# ch634x.net
KiCad netlist of a schematic drawn in Altium Designer
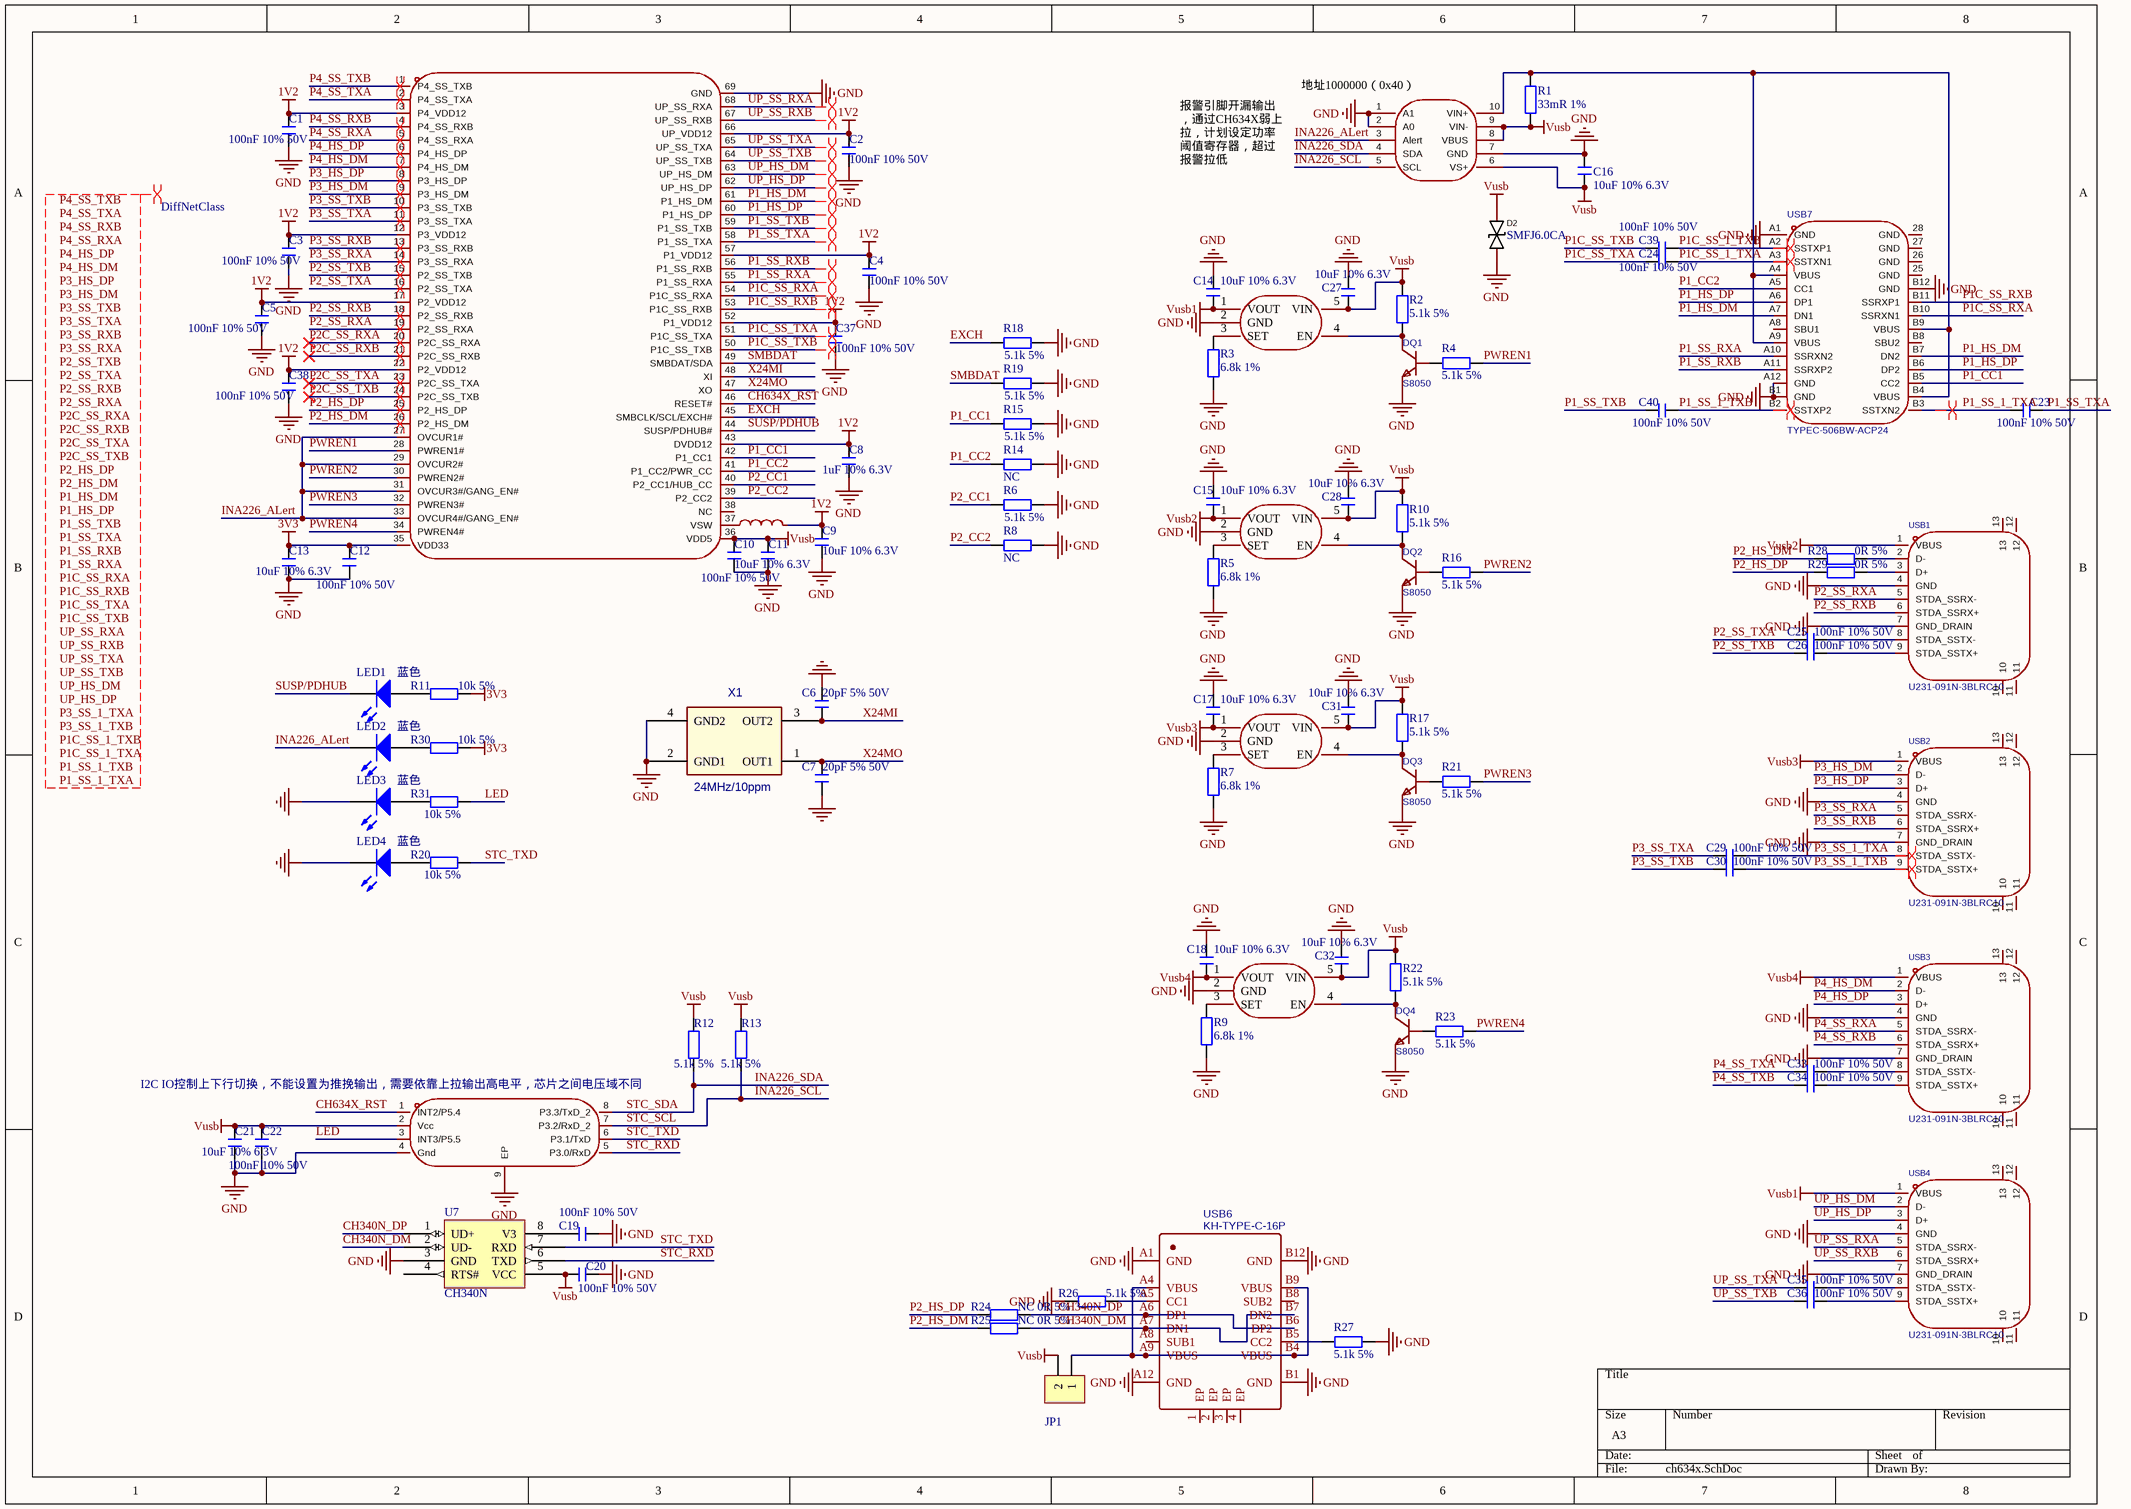
[diagram p0: ch634x.SchDoc]

(export (version "E")
  (design (tool "Eeschema 10.0.6"))
  (components
    (comp (ref "C1")
      (value "100nF 10% 50V")
      (footprint "C0603_L")
      (description "贴片电容")
      (libsource (lib "0.1 - 电阻-电容-电感") (part "C"))
    )
    (comp (ref "C2")
      (value "100nF 10% 50V")
      (footprint "C0603_L")
      (description "贴片电容")
      (libsource (lib "0.1 - 电阻-电容-电感") (part "C"))
    )
    (comp (ref "C3")
      (value "100nF 10% 50V")
      (footprint "C0603_L")
      (description "贴片电容")
      (libsource (lib "0.1 - 电阻-电容-电感") (part "C"))
    )
    (comp (ref "C4")
      (value "100nF 10% 50V")
      (footprint "C0603_L")
      (description "贴片电容")
      (libsource (lib "0.1 - 电阻-电容-电感") (part "C"))
    )
    (comp (ref "C5")
      (value "100nF 10% 50V")
      (footprint "C0603_L")
      (description "贴片电容")
      (libsource (lib "0.1 - 电阻-电容-电感") (part "C"))
    )
    (comp (ref "C6")
      (value "20pF 5% 50V")
      (footprint "C0603_L")
      (description "贴片电容")
      (libsource (lib "0.1 - 电阻-电容-电感") (part "C"))
    )
    (comp (ref "C7")
      (value "20pF 5% 50V")
      (footprint "C0603_L")
      (description "贴片电容")
      (libsource (lib "0.1 - 电阻-电容-电感") (part "C"))
    )
    (comp (ref "C8")
      (value "1uF 10% 6.3V")
      (footprint "C0603_L")
      (description "贴片电容")
      (libsource (lib "0.1 - 电阻-电容-电感") (part "C"))
    )
    (comp (ref "C9")
      (value "10uF 10% 6.3V")
      (footprint "C0603_L")
      (description "贴片电容")
      (libsource (lib "0.1 - 电阻-电容-电感") (part "C"))
    )
    (comp (ref "C10")
      (value "100nF 10% 50V")
      (footprint "C0603_L")
      (description "贴片电容")
      (libsource (lib "0.1 - 电阻-电容-电感") (part "C"))
    )
    (comp (ref "C11")
      (value "10uF 10% 6.3V")
      (footprint "C0603_L")
      (description "贴片电容")
      (libsource (lib "0.1 - 电阻-电容-电感") (part "C"))
    )
    (comp (ref "C12")
      (value "100nF 10% 50V")
      (footprint "C0603_L")
      (description "贴片电容")
      (libsource (lib "0.1 - 电阻-电容-电感") (part "C"))
    )
    (comp (ref "C13")
      (value "10uF 10% 6.3V")
      (footprint "C0603_L")
      (description "贴片电容")
      (libsource (lib "0.1 - 电阻-电容-电感") (part "C"))
    )
    (comp (ref "C14")
      (value "10uF 10% 6.3V")
      (footprint "C0603_L")
      (description "贴片电容")
      (libsource (lib "0.1 - 电阻-电容-电感") (part "C"))
    )
    (comp (ref "C15")
      (value "10uF 10% 6.3V")
      (footprint "C0603_L")
      (description "贴片电容")
      (libsource (lib "0.1 - 电阻-电容-电感") (part "C"))
    )
    (comp (ref "C16")
      (value "10uF 10% 6.3V")
      (footprint "C0603_L")
      (description "贴片电容")
      (libsource (lib "0.1 - 电阻-电容-电感") (part "C"))
    )
    (comp (ref "C17")
      (value "10uF 10% 6.3V")
      (footprint "C0603_L")
      (description "贴片电容")
      (libsource (lib "0.1 - 电阻-电容-电感") (part "C"))
    )
    (comp (ref "C18")
      (value "10uF 10% 6.3V")
      (footprint "C0603_L")
      (description "贴片电容")
      (libsource (lib "0.1 - 电阻-电容-电感") (part "C"))
    )
    (comp (ref "C19")
      (value "100nF 10% 50V")
      (footprint "C0603_L")
      (description "贴片电容")
      (libsource (lib "0.1 - 电阻-电容-电感") (part "C"))
    )
    (comp (ref "C20")
      (value "100nF 10% 50V")
      (footprint "C0603_L")
      (description "贴片电容")
      (libsource (lib "0.1 - 电阻-电容-电感") (part "C"))
    )
    (comp (ref "C21")
      (value "10uF 10% 6.3V")
      (footprint "C0603_L")
      (description "贴片电容")
      (libsource (lib "0.1 - 电阻-电容-电感") (part "C"))
    )
    (comp (ref "C22")
      (value "100nF 10% 50V")
      (footprint "C0603_L")
      (description "贴片电容")
      (libsource (lib "0.1 - 电阻-电容-电感") (part "C"))
    )
    (comp (ref "C23")
      (value "100nF 10% 50V")
      (footprint "R0402_L")
      (description "贴片电容")
      (libsource (lib "0.1 - 电阻-电容-电感") (part "C"))
    )
    (comp (ref "C24")
      (value "100nF 10% 50V")
      (footprint "R0402_L")
      (description "贴片电容")
      (libsource (lib "0.1 - 电阻-电容-电感") (part "C"))
    )
    (comp (ref "C25")
      (value "100nF 10% 50V")
      (footprint "C0402_L")
      (description "贴片电容")
      (libsource (lib "0.1 - 电阻-电容-电感") (part "C"))
    )
    (comp (ref "C26")
      (value "100nF 10% 50V")
      (footprint "C0402_L")
      (description "贴片电容")
      (libsource (lib "0.1 - 电阻-电容-电感") (part "C"))
    )
    (comp (ref "C27")
      (value "10uF 10% 6.3V")
      (footprint "C0603_L")
      (description "贴片电容")
      (libsource (lib "0.1 - 电阻-电容-电感") (part "C"))
    )
    (comp (ref "C28")
      (value "10uF 10% 6.3V")
      (footprint "C0603_L")
      (description "贴片电容")
      (libsource (lib "0.1 - 电阻-电容-电感") (part "C"))
    )
    (comp (ref "C29")
      (value "100nF 10% 50V")
      (footprint "C0402_L")
      (description "贴片电容")
      (libsource (lib "0.1 - 电阻-电容-电感") (part "C"))
    )
    (comp (ref "C30")
      (value "100nF 10% 50V")
      (footprint "C0402_L")
      (description "贴片电容")
      (libsource (lib "0.1 - 电阻-电容-电感") (part "C"))
    )
    (comp (ref "C31")
      (value "10uF 10% 6.3V")
      (footprint "C0603_L")
      (description "贴片电容")
      (libsource (lib "0.1 - 电阻-电容-电感") (part "C"))
    )
    (comp (ref "C32")
      (value "10uF 10% 6.3V")
      (footprint "C0603_L")
      (description "贴片电容")
      (libsource (lib "0.1 - 电阻-电容-电感") (part "C"))
    )
    (comp (ref "C33")
      (value "100nF 10% 50V")
      (footprint "C0402_L")
      (description "贴片电容")
      (libsource (lib "0.1 - 电阻-电容-电感") (part "C"))
    )
    (comp (ref "C34")
      (value "100nF 10% 50V")
      (footprint "C0402_L")
      (description "贴片电容")
      (libsource (lib "0.1 - 电阻-电容-电感") (part "C"))
    )
    (comp (ref "C35")
      (value "100nF 10% 50V")
      (footprint "C0402_L")
      (description "贴片电容")
      (libsource (lib "0.1 - 电阻-电容-电感") (part "C"))
    )
    (comp (ref "C36")
      (value "100nF 10% 50V")
      (footprint "C0402_L")
      (description "贴片电容")
      (libsource (lib "0.1 - 电阻-电容-电感") (part "C"))
    )
    (comp (ref "C37")
      (value "100nF 10% 50V")
      (footprint "C0603_L")
      (description "贴片电容")
      (libsource (lib "0.1 - 电阻-电容-电感") (part "C"))
    )
    (comp (ref "C38")
      (value "100nF 10% 50V")
      (footprint "C0603_L")
      (description "贴片电容")
      (libsource (lib "0.1 - 电阻-电容-电感") (part "C"))
    )
    (comp (ref "C39")
      (value "100nF 10% 50V")
      (footprint "R0402_L")
      (description "贴片电容")
      (libsource (lib "0.1 - 电阻-电容-电感") (part "C"))
    )
    (comp (ref "C40")
      (value "100nF 10% 50V")
      (footprint "R0402_L")
      (description "贴片电容")
      (libsource (lib "0.1 - 电阻-电容-电感") (part "C"))
    )
    (comp (ref "D2")
      (value "SMFJ6.0CA")
      (footprint "SOD-123F_L2.8-W1.8-LS3.7-RD")
      (description "瞬态抑制二极管")
      (fields (field (name "MANUFACTURER") "BORN伯恩半导体") (field (name "MANUFACTURER PART") "SMFJ6.5CA"))
      (libsource (lib "altium-import") (part "root_1_SMFJ6.5CA_"))
    )
    (comp (ref "DQ1")
      (value "S8050")
      (footprint "SOT-23-3_L2.9-W1.6-P1.90-LS2.8-BR")
      (description "贴片三极管")
      (fields (field (name "BOM_SUPPLIER PART") "C181158") (field (name "CONTRIBUTOR") "LCSC"))
      (libsource (lib "altium-import") (part "root_0_mirrored_S8050_"))
    )
    (comp (ref "DQ2")
      (value "S8050")
      (footprint "SOT-23-3_L2.9-W1.6-P1.90-LS2.8-BR")
      (description "贴片三极管")
      (fields (field (name "BOM_SUPPLIER PART") "C181158") (field (name "CONTRIBUTOR") "LCSC"))
      (libsource (lib "altium-import") (part "root_0_mirrored_S8050_"))
    )
    (comp (ref "DQ3")
      (value "S8050")
      (footprint "SOT-23-3_L2.9-W1.6-P1.90-LS2.8-BR")
      (description "贴片三极管")
      (fields (field (name "BOM_SUPPLIER PART") "C181158") (field (name "CONTRIBUTOR") "LCSC"))
      (libsource (lib "altium-import") (part "root_0_mirrored_S8050_"))
    )
    (comp (ref "DQ4")
      (value "S8050")
      (footprint "SOT-23-3_L2.9-W1.6-P1.90-LS2.8-BR")
      (description "贴片三极管")
      (fields (field (name "BOM_SUPPLIER PART") "C181158") (field (name "CONTRIBUTOR") "LCSC"))
      (libsource (lib "altium-import") (part "root_0_mirrored_S8050_"))
    )
    (comp (ref "JP1")
      (value "HDR-1X2")
      (footprint "HDR2.54-LI-2P")
      (description "2P接插件")
      (libsource (lib "5.5 - 2.54mm连接器(KF2EDGK_XH2.54_2.54排针排母)") (part "Header 2"))
    )
    (comp (ref "L1")
      (value "ftc252012s100mbca")
      (footprint "IND-SMD_L2.5-W2.0")
      (description "电感值:10uH;精度:±20%;额定电流:1.2A;饱和电流(Isat):1.6A;类型:一体成型电感;")
      (fields
        (field (name "MANUFACTURER") "cjiang(长江微电)")
        (field (name "MANUFACTURERPART") "FTC252012S100MBCA")
      )
      (libsource (lib "altium-import") (part "root_0_ftc252012s100mbca_"))
    )
    (comp (ref "LED1")
      (value "蓝色")
      (footprint "LED0603-FD")
      (description "贴片LED")
      (libsource (lib "0.3 - LED发光二极管-IR二极管_接收管-光耦") (part "LED"))
    )
    (comp (ref "LED2")
      (value "蓝色")
      (footprint "LED0603-FD")
      (description "贴片LED")
      (libsource (lib "0.3 - LED发光二极管-IR二极管_接收管-光耦") (part "LED"))
    )
    (comp (ref "LED3")
      (value "蓝色")
      (footprint "LED0603-FD")
      (description "贴片LED")
      (libsource (lib "0.3 - LED发光二极管-IR二极管_接收管-光耦") (part "LED"))
    )
    (comp (ref "LED4")
      (value "蓝色")
      (footprint "LED0603-FD")
      (description "贴片LED")
      (libsource (lib "0.3 - LED发光二极管-IR二极管_接收管-光耦") (part "LED"))
    )
    (comp (ref "R1")
      (value "33mR 1%")
      (footprint "R1206_L")
      (description "FRM121WFR033TM")
      (libsource (lib "0.1 - 电阻-电容-电感") (part "R"))
    )
    (comp (ref "R2")
      (value "5.1k 5%")
      (footprint "R0603_L")
      (description "贴片电阻")
      (libsource (lib "0.1 - 电阻-电容-电感") (part "R"))
    )
    (comp (ref "R3")
      (value "6.8k 1%")
      (footprint "R0603_L")
      (description "贴片电阻")
      (libsource (lib "0.1 - 电阻-电容-电感") (part "R"))
    )
    (comp (ref "R4")
      (value "5.1k 5%")
      (footprint "R0603_L")
      (description "贴片电阻")
      (libsource (lib "0.1 - 电阻-电容-电感") (part "R"))
    )
    (comp (ref "R5")
      (value "6.8k 1%")
      (footprint "R0603_L")
      (description "贴片电阻")
      (libsource (lib "0.1 - 电阻-电容-电感") (part "R"))
    )
    (comp (ref "R6")
      (value "5.1k 5%")
      (footprint "R0603_L")
      (description "贴片电阻")
      (libsource (lib "0.1 - 电阻-电容-电感") (part "R"))
    )
    (comp (ref "R7")
      (value "6.8k 1%")
      (footprint "R0603_L")
      (description "贴片电阻")
      (libsource (lib "0.1 - 电阻-电容-电感") (part "R"))
    )
    (comp (ref "R8")
      (value "NC")
      (footprint "R0603_L")
      (description "贴片电阻")
      (libsource (lib "0.1 - 电阻-电容-电感") (part "R"))
    )
    (comp (ref "R9")
      (value "6.8k 1%")
      (footprint "R0603_L")
      (description "贴片电阻")
      (libsource (lib "0.1 - 电阻-电容-电感") (part "R"))
    )
    (comp (ref "R10")
      (value "5.1k 5%")
      (footprint "R0603_L")
      (description "贴片电阻")
      (libsource (lib "0.1 - 电阻-电容-电感") (part "R"))
    )
    (comp (ref "R11")
      (value "10k 5%")
      (footprint "R0603_L")
      (description "贴片电阻")
      (libsource (lib "0.1 - 电阻-电容-电感") (part "R"))
    )
    (comp (ref "R12")
      (value "5.1k 5%")
      (footprint "R0603_L")
      (description "贴片电阻")
      (libsource (lib "0.1 - 电阻-电容-电感") (part "R"))
    )
    (comp (ref "R13")
      (value "5.1k 5%")
      (footprint "R0603_L")
      (description "贴片电阻")
      (libsource (lib "0.1 - 电阻-电容-电感") (part "R"))
    )
    (comp (ref "R14")
      (value "NC")
      (footprint "R0603_L")
      (description "贴片电阻")
      (libsource (lib "0.1 - 电阻-电容-电感") (part "R"))
    )
    (comp (ref "R15")
      (value "5.1k 5%")
      (footprint "R0603_L")
      (description "贴片电阻")
      (libsource (lib "0.1 - 电阻-电容-电感") (part "R"))
    )
    (comp (ref "R16")
      (value "5.1k 5%")
      (footprint "R0603_L")
      (description "贴片电阻")
      (libsource (lib "0.1 - 电阻-电容-电感") (part "R"))
    )
    (comp (ref "R17")
      (value "5.1k 5%")
      (footprint "R0603_L")
      (description "贴片电阻")
      (libsource (lib "0.1 - 电阻-电容-电感") (part "R"))
    )
    (comp (ref "R18")
      (value "5.1k 5%")
      (footprint "R0603_L")
      (description "贴片电阻")
      (libsource (lib "0.1 - 电阻-电容-电感") (part "R"))
    )
    (comp (ref "R19")
      (value "5.1k 5%")
      (footprint "R0603_L")
      (description "贴片电阻")
      (libsource (lib "0.1 - 电阻-电容-电感") (part "R"))
    )
    (comp (ref "R20")
      (value "10k 5%")
      (footprint "R0603_L")
      (description "贴片电阻")
      (libsource (lib "0.1 - 电阻-电容-电感") (part "R"))
    )
    (comp (ref "R21")
      (value "5.1k 5%")
      (footprint "R0603_L")
      (description "贴片电阻")
      (libsource (lib "0.1 - 电阻-电容-电感") (part "R"))
    )
    (comp (ref "R22")
      (value "5.1k 5%")
      (footprint "R0603_L")
      (description "贴片电阻")
      (libsource (lib "0.1 - 电阻-电容-电感") (part "R"))
    )
    (comp (ref "R23")
      (value "5.1k 5%")
      (footprint "R0603_L")
      (description "贴片电阻")
      (libsource (lib "0.1 - 电阻-电容-电感") (part "R"))
    )
    (comp (ref "R24")
      (value "NC 0R 5%")
      (footprint "R0603_L")
      (description "贴片电阻")
      (libsource (lib "0.1 - 电阻-电容-电感") (part "R"))
    )
    (comp (ref "R25")
      (value "NC 0R 5%")
      (footprint "R0603_L")
      (description "贴片电阻")
      (libsource (lib "0.1 - 电阻-电容-电感") (part "R"))
    )
    (comp (ref "R26")
      (value "5.1k 5%")
      (footprint "R0603_L")
      (description "贴片电阻")
      (libsource (lib "0.1 - 电阻-电容-电感") (part "R"))
    )
    (comp (ref "R27")
      (value "5.1k 5%")
      (footprint "R0603_L")
      (description "贴片电阻")
      (libsource (lib "0.1 - 电阻-电容-电感") (part "R"))
    )
    (comp (ref "R28")
      (value "0R 5%")
      (footprint "R0603_L")
      (description "贴片电阻")
      (libsource (lib "0.1 - 电阻-电容-电感") (part "R"))
    )
    (comp (ref "R29")
      (value "0R 5%")
      (footprint "R0603_L")
      (description "贴片电阻")
      (libsource (lib "0.1 - 电阻-电容-电感") (part "R"))
    )
    (comp (ref "R30")
      (value "10k 5%")
      (footprint "R0603_L")
      (description "贴片电阻")
      (libsource (lib "0.1 - 电阻-电容-电感") (part "R"))
    )
    (comp (ref "R31")
      (value "10k 5%")
      (footprint "R0603_L")
      (description "贴片电阻")
      (libsource (lib "0.1 - 电阻-电容-电感") (part "R"))
    )
    (comp (ref "U1")
      (value "ch634x_c48985831")
      (footprint "QFN-68_L8.0-W8.0-P0.40-BL-EP6.2")
      (fields (field (name "MANUFACTURER") "WCH(南京沁恒)") (field (name "MANUFACTURERPART") "CH634X"))
      (libsource (lib "altium-import") (part "root_0_ch634x_c48985831_"))
    )
    (comp (ref "U2")
      (value "MT9700")
      (footprint "SOT-23-5_L3.0-W1.7-P0.95-LS2.8-BR")
      (fields (field (name "MANUFACTURER") "西安航天民芯"))
      (libsource (lib "Schlib1") (part "MT9700"))
    )
    (comp (ref "U3")
      (value "MT9700")
      (footprint "SOT-23-5_L3.0-W1.7-P0.95-LS2.8-BR")
      (fields (field (name "MANUFACTURER") "西安航天民芯"))
      (libsource (lib "Schlib1") (part "MT9700"))
    )
    (comp (ref "U4")
      (value "ina226aidgsr")
      (footprint "MSOP-10_L3.0-W3.0-P0.50-LS5.0-BL")
      (description "放大器数:-;共模电压:0V~36V;增益:-;带宽(-3db):-;")
      (fields (field (name "MANUFACTURER") "TI(德州仪器)") (field (name "MANUFACTURERPART") "INA226AIDGSR"))
      (libsource (lib "altium-import") (part "root_0_ina226aidgsr_"))
    )
    (comp (ref "U5")
      (value "MT9700")
      (footprint "SOT-23-5_L3.0-W1.7-P0.95-LS2.8-BR")
      (fields (field (name "MANUFACTURER") "西安航天民芯"))
      (libsource (lib "Schlib1") (part "MT9700"))
    )
    (comp (ref "U6")
      (value "MT9700")
      (footprint "SOT-23-5_L3.0-W1.7-P0.95-LS2.8-BR")
      (fields (field (name "MANUFACTURER") "西安航天民芯"))
      (libsource (lib "Schlib1") (part "MT9700"))
    )
    (comp (ref "U7") (value "CH340N") (footprint "SOP8") (libsource (lib "Schlib1") (part "CH340N")))
    (comp (ref "U8")
      (value "stc8g1k08-36i-dfn8")
      (footprint "DFN-8_L3.0-W3.0-P0.50-BL-EP")
      (description "CPU内核:51系列;应用领域:-;")
      (fields (field (name "MANUFACTURER") "STC") (field (name "MANUFACTURERPART") "STC8G1K08-36I-DFN8"))
      (libsource (lib "altium-import") (part "root_0_stc8g1k08-36i-dfn8_"))
    )
    (comp (ref "USB1")
      (value "U231-091N-3BLRC10")
      (footprint "USB-A-TH_U231-091N-5")
      (description "连接器类型:Type-A;协议标准:-;公母:母;安装方式:弯插;触点数量:9P;端口数量:1;额定电流 - 电源:3A;工作温度:-40℃~+85℃;")
      (fields (field (name "MANUFACTURER") "XKB Connection(中国星坤)"))
      (libsource (lib "altium-import") (part "root_0_U231-091N-3BLRC10_"))
    )
    (comp (ref "USB2")
      (value "U231-091N-3BLRC10")
      (footprint "USB-A-TH_U231-091N-5")
      (description "连接器类型:Type-A;协议标准:-;公母:母;安装方式:弯插;触点数量:9P;端口数量:1;额定电流 - 电源:3A;工作温度:-40℃~+85℃;")
      (fields (field (name "MANUFACTURER") "XKB Connection(中国星坤)"))
      (libsource (lib "altium-import") (part "root_0_U231-091N-3BLRC10_"))
    )
    (comp (ref "USB3")
      (value "U231-091N-3BLRC10")
      (footprint "USB-A-TH_U231-091N-5")
      (description "连接器类型:Type-A;协议标准:-;公母:母;安装方式:弯插;触点数量:9P;端口数量:1;额定电流 - 电源:3A;工作温度:-40℃~+85℃;")
      (fields (field (name "MANUFACTURER") "XKB Connection(中国星坤)"))
      (libsource (lib "altium-import") (part "root_0_U231-091N-3BLRC10_"))
    )
    (comp (ref "USB4")
      (value "U231-091N-3BLRC10")
      (footprint "USB-A-TH_U231-091N-5")
      (description "连接器类型:Type-A;协议标准:-;公母:母;安装方式:弯插;触点数量:9P;端口数量:1;额定电流 - 电源:3A;工作温度:-40℃~+85℃;")
      (fields (field (name "MANUFACTURER") "XKB Connection(中国星坤)"))
      (libsource (lib "altium-import") (part "root_0_U231-091N-3BLRC10_"))
    )
    (comp (ref "USB6")
      (value "KH-TYPE-C-16P")
      (footprint "KH-TYPE-C")
      (fields (field (name "BOM_SUPPLIER PART") "C709357") (field (name "CONTRIBUTOR") "LCSC"))
      (libsource (lib "altium-import") (part "root_0_KH-TYPE-C-16P_"))
    )
    (comp (ref "USB7")
      (value "TYPEC-506BW-ACP24")
      (footprint "USB-C-SMD_TYPEC-506BW-ACP24")
      (description "连接器类型:Type-C;协议标准:USB 3.1;公母:母;安装方式:卧贴;触点数量:24P;端口数量:1;额定电流 - 电源:3A;工作温度:-25℃~+85℃;")
      (fields (field (name "MANUFACTURER") "XUNPU(讯普)"))
      (libsource (lib "altium-import") (part "root_0_TYPEC-506BW-ACP24_"))
    )
    (comp (ref "X1")
      (value "24MHz/10ppm")
      (footprint "OSC-3225-4P")
      (description "晶振")
      (libsource (lib "*") (part "OSC44M_5"))
    )
  )
  (nets
    (net (code "1") (name "/CH340N_DM") (class "Default")
      (node (ref "R25") (pin "2") (pinfunction "2_2") (pintype "passive"))
      (node (ref "U7") (pin "2") (pinfunction "UD-_2") (pintype "bidirectional"))
      (node (ref "USB6") (pin "A7") (pinfunction "DN1_A7") (pintype "passive"))
      (node (ref "USB6") (pin "B7") (pinfunction "DN2_B7") (pintype "passive"))
    )
    (net (code "2") (name "/CH340N_DP") (class "Default")
      (node (ref "R24") (pin "2") (pinfunction "2_2") (pintype "passive"))
      (node (ref "U7") (pin "1") (pinfunction "UD+_1") (pintype "bidirectional"))
      (node (ref "USB6") (pin "A6") (pinfunction "DP1_A6") (pintype "passive"))
      (node (ref "USB6") (pin "B6") (pinfunction "DP2_B6") (pintype "passive"))
    )
    (net (code "3") (name "/CH634X_RST") (class "Default")
      (node (ref "U1") (pin "46") (pinfunction "RESET#_46") (pintype "passive"))
      (node (ref "U8") (pin "1") (pinfunction "INT2/P5.4_1") (pintype "passive"))
    )
    (net (code "4") (name "/EXCH") (class "Default")
      (node (ref "R18") (pin "1") (pinfunction "1_1") (pintype "passive"))
      (node (ref "U1") (pin "45") (pinfunction "SMBCLK/SCL/EXCH#_45") (pintype "passive"))
    )
    (net (code "5") (name "/INA226_ALert") (class "Default")
      (node (ref "LED2") (pin "2") (pinfunction "K_2") (pintype "passive"))
      (node (ref "U1") (pin "27") (pinfunction "OVCUR1#_27") (pintype "passive"))
      (node (ref "U1") (pin "29") (pinfunction "OVCUR2#_29") (pintype "passive"))
      (node (ref "U1") (pin "31") (pinfunction "OVCUR3#/GANG_EN#_31") (pintype "passive"))
      (node (ref "U1") (pin "33") (pinfunction "OVCUR4#/GANG_EN#_33") (pintype "passive"))
      (node (ref "U4") (pin "3") (pinfunction "Alert_3") (pintype "passive"))
    )
    (net (code "6") (name "/INA226_SCL") (class "Default")
      (node (ref "R13") (pin "2") (pinfunction "2_2") (pintype "passive"))
      (node (ref "U4") (pin "5") (pinfunction "SCL_5") (pintype "passive"))
      (node (ref "U8") (pin "7") (pinfunction "P3.2/RxD_2_7") (pintype "passive"))
    )
    (net (code "7") (name "/INA226_SDA") (class "Default")
      (node (ref "R12") (pin "2") (pinfunction "2_2") (pintype "passive"))
      (node (ref "U4") (pin "4") (pinfunction "SDA_4") (pintype "passive"))
      (node (ref "U8") (pin "8") (pinfunction "P3.3/TxD_2_8") (pintype "passive"))
    )
    (net (code "8") (name "/LED") (class "Default")
      (node (ref "R31") (pin "1") (pinfunction "1_1") (pintype "passive"))
      (node (ref "U8") (pin "3") (pinfunction "INT3/P5.5_3") (pintype "passive"))
    )
    (net (code "9") (name "/P1C_SS_1_TXA") (class "Default")
      (node (ref "C24") (pin "2") (pinfunction "2_2") (pintype "passive"))
      (node (ref "USB7") (pin "A3") (pinfunction "SSTXN1_A3") (pintype "passive"))
    )
    (net (code "10") (name "/P1C_SS_1_TXB") (class "Default")
      (node (ref "C39") (pin "2") (pinfunction "2_2") (pintype "passive"))
      (node (ref "USB7") (pin "A2") (pinfunction "SSTXP1_A2") (pintype "passive"))
    )
    (net (code "11") (name "/P1C_SS_RXA") (class "Default")
      (node (ref "U1") (pin "54") (pinfunction "P1C_SS_RXA_54") (pintype "passive"))
      (node (ref "USB7") (pin "B10") (pinfunction "SSRXN1_B10") (pintype "passive"))
    )
    (net (code "12") (name "/P1C_SS_RXB") (class "Default")
      (node (ref "U1") (pin "53") (pinfunction "P1C_SS_RXB_53") (pintype "passive"))
      (node (ref "USB7") (pin "B11") (pinfunction "SSRXP1_B11") (pintype "passive"))
    )
    (net (code "13") (name "/P1C_SS_TXA") (class "Default")
      (node (ref "C24") (pin "1") (pinfunction "1_1") (pintype "passive"))
      (node (ref "U1") (pin "51") (pinfunction "P1C_SS_TXA_51") (pintype "passive"))
    )
    (net (code "14") (name "/P1C_SS_TXB") (class "Default")
      (node (ref "C39") (pin "1") (pinfunction "1_1") (pintype "passive"))
      (node (ref "U1") (pin "50") (pinfunction "P1C_SS_TXB_50") (pintype "passive"))
    )
    (net (code "15") (name "/P1_CC1") (class "Default")
      (node (ref "R15") (pin "1") (pinfunction "1_1") (pintype "passive"))
      (node (ref "U1") (pin "42") (pinfunction "P1_CC1_42") (pintype "passive"))
      (node (ref "USB7") (pin "B5") (pinfunction "CC2_B5") (pintype "passive"))
    )
    (net (code "16") (name "/P1_CC2") (class "Default")
      (node (ref "R14") (pin "1") (pinfunction "1_1") (pintype "passive"))
      (node (ref "U1") (pin "41") (pinfunction "P1_CC2/PWR_CC_41") (pintype "passive"))
      (node (ref "USB7") (pin "A5") (pinfunction "CC1_A5") (pintype "passive"))
    )
    (net (code "17") (name "/P1_HS_DM") (class "Default")
      (node (ref "U1") (pin "61") (pinfunction "P1_HS_DM_61") (pintype "passive"))
      (node (ref "USB7") (pin "A7") (pinfunction "DN1_A7") (pintype "passive"))
      (node (ref "USB7") (pin "B7") (pinfunction "DN2_B7") (pintype "passive"))
    )
    (net (code "18") (name "/P1_HS_DP") (class "Default")
      (node (ref "U1") (pin "60") (pinfunction "P1_HS_DP_60") (pintype "passive"))
      (node (ref "USB7") (pin "A6") (pinfunction "DP1_A6") (pintype "passive"))
      (node (ref "USB7") (pin "B6") (pinfunction "DP2_B6") (pintype "passive"))
    )
    (net (code "19") (name "/P1_SS_1_TXA") (class "Default")
      (node (ref "C23") (pin "1") (pinfunction "1_1") (pintype "passive"))
      (node (ref "USB7") (pin "B3") (pinfunction "SSTXN2_B3") (pintype "passive"))
    )
    (net (code "20") (name "/P1_SS_1_TXB") (class "Default")
      (node (ref "C40") (pin "2") (pinfunction "2_2") (pintype "passive"))
      (node (ref "USB7") (pin "B2") (pinfunction "SSTXP2_B2") (pintype "passive"))
    )
    (net (code "21") (name "/P1_SS_RXA") (class "Default")
      (node (ref "U1") (pin "55") (pinfunction "P1_SS_RXA_55") (pintype "passive"))
      (node (ref "USB7") (pin "A10") (pinfunction "SSRXN2_A10") (pintype "passive"))
    )
    (net (code "22") (name "/P1_SS_RXB") (class "Default")
      (node (ref "U1") (pin "56") (pinfunction "P1_SS_RXB_56") (pintype "passive"))
      (node (ref "USB7") (pin "A11") (pinfunction "SSRXP2_A11") (pintype "passive"))
    )
    (net (code "23") (name "/P1_SS_TXA") (class "Default")
      (node (ref "C23") (pin "2") (pinfunction "2_2") (pintype "passive"))
      (node (ref "U1") (pin "58") (pinfunction "P1_SS_TXA_58") (pintype "passive"))
    )
    (net (code "24") (name "/P1_SS_TXB") (class "Default")
      (node (ref "C40") (pin "1") (pinfunction "1_1") (pintype "passive"))
      (node (ref "U1") (pin "59") (pinfunction "P1_SS_TXB_59") (pintype "passive"))
    )
    (net (code "25") (name "/P2C_SS_RXA") (class "Default")
      (node (ref "U1") (pin "20") (pinfunction "P2C_SS_RXA_20") (pintype "passive+no_connect"))
    )
    (net (code "26") (name "/P2C_SS_RXB") (class "Default")
      (node (ref "U1") (pin "21") (pinfunction "P2C_SS_RXB_21") (pintype "passive+no_connect"))
    )
    (net (code "27") (name "/P2C_SS_TXA") (class "Default")
      (node (ref "U1") (pin "23") (pinfunction "P2C_SS_TXA_23") (pintype "passive+no_connect"))
    )
    (net (code "28") (name "/P2C_SS_TXB") (class "Default")
      (node (ref "U1") (pin "24") (pinfunction "P2C_SS_TXB_24") (pintype "passive+no_connect"))
    )
    (net (code "29") (name "/P2_CC1") (class "Default")
      (node (ref "R6") (pin "1") (pinfunction "1_1") (pintype "passive"))
      (node (ref "U1") (pin "40") (pinfunction "P2_CC1/HUB_CC_40") (pintype "passive"))
    )
    (net (code "30") (name "/P2_CC2") (class "Default")
      (node (ref "R8") (pin "1") (pinfunction "1_1") (pintype "passive"))
      (node (ref "U1") (pin "39") (pinfunction "P2_CC2_39") (pintype "passive"))
    )
    (net (code "31") (name "/P2_HS_DM") (class "Default")
      (node (ref "R25") (pin "1") (pinfunction "1_1") (pintype "passive"))
      (node (ref "R28") (pin "1") (pinfunction "1_1") (pintype "passive"))
      (node (ref "U1") (pin "26") (pinfunction "P2_HS_DM_26") (pintype "passive"))
    )
    (net (code "32") (name "/P2_HS_DP") (class "Default")
      (node (ref "R24") (pin "1") (pinfunction "1_1") (pintype "passive"))
      (node (ref "R29") (pin "1") (pinfunction "1_1") (pintype "passive"))
      (node (ref "U1") (pin "25") (pinfunction "P2_HS_DP_25") (pintype "passive"))
    )
    (net (code "33") (name "/P2_SS_RXA") (class "Default")
      (node (ref "U1") (pin "19") (pinfunction "P2_SS_RXA_19") (pintype "passive"))
      (node (ref "USB1") (pin "5") (pinfunction "STDA_SSRX-_5") (pintype "passive"))
    )
    (net (code "34") (name "/P2_SS_RXB") (class "Default")
      (node (ref "U1") (pin "18") (pinfunction "P2_SS_RXB_18") (pintype "passive"))
      (node (ref "USB1") (pin "6") (pinfunction "STDA_SSRX+_6") (pintype "passive"))
    )
    (net (code "35") (name "/P2_SS_TXA") (class "Default")
      (node (ref "C25") (pin "1") (pinfunction "1_1") (pintype "passive"))
      (node (ref "U1") (pin "16") (pinfunction "P2_SS_TXA_16") (pintype "passive"))
    )
    (net (code "36") (name "/P2_SS_TXB") (class "Default")
      (node (ref "C26") (pin "1") (pinfunction "1_1") (pintype "passive"))
      (node (ref "U1") (pin "15") (pinfunction "P2_SS_TXB_15") (pintype "passive"))
    )
    (net (code "37") (name "/P3_HS_DM") (class "Default")
      (node (ref "U1") (pin "9") (pinfunction "P3_HS_DM_9") (pintype "passive"))
      (node (ref "USB2") (pin "2") (pinfunction "D-_2") (pintype "passive"))
    )
    (net (code "38") (name "/P3_HS_DP") (class "Default")
      (node (ref "U1") (pin "8") (pinfunction "P3_HS_DP_8") (pintype "passive"))
      (node (ref "USB2") (pin "3") (pinfunction "D+_3") (pintype "passive"))
    )
    (net (code "39") (name "/P3_SS_1_TXA") (class "Default")
      (node (ref "C29") (pin "2") (pinfunction "2_2") (pintype "passive"))
      (node (ref "USB2") (pin "8") (pinfunction "STDA_SSTX-_8") (pintype "passive"))
    )
    (net (code "40") (name "/P3_SS_1_TXB") (class "Default")
      (node (ref "C30") (pin "2") (pinfunction "2_2") (pintype "passive"))
      (node (ref "USB2") (pin "9") (pinfunction "STDA_SSTX+_9") (pintype "passive"))
    )
    (net (code "41") (name "/P3_SS_RXA") (class "Default")
      (node (ref "U1") (pin "14") (pinfunction "P3_SS_RXA_14") (pintype "passive"))
      (node (ref "USB2") (pin "5") (pinfunction "STDA_SSRX-_5") (pintype "passive"))
    )
    (net (code "42") (name "/P3_SS_RXB") (class "Default")
      (node (ref "U1") (pin "13") (pinfunction "P3_SS_RXB_13") (pintype "passive"))
      (node (ref "USB2") (pin "6") (pinfunction "STDA_SSRX+_6") (pintype "passive"))
    )
    (net (code "43") (name "/P3_SS_TXA") (class "Default")
      (node (ref "C29") (pin "1") (pinfunction "1_1") (pintype "passive"))
      (node (ref "U1") (pin "11") (pinfunction "P3_SS_TXA_11") (pintype "passive"))
    )
    (net (code "44") (name "/P3_SS_TXB") (class "Default")
      (node (ref "C30") (pin "1") (pinfunction "1_1") (pintype "passive"))
      (node (ref "U1") (pin "10") (pinfunction "P3_SS_TXB_10") (pintype "passive"))
    )
    (net (code "45") (name "/P4_HS_DM") (class "Default")
      (node (ref "U1") (pin "7") (pinfunction "P4_HS_DM_7") (pintype "passive"))
      (node (ref "USB3") (pin "2") (pinfunction "D-_2") (pintype "passive"))
    )
    (net (code "46") (name "/P4_HS_DP") (class "Default")
      (node (ref "U1") (pin "6") (pinfunction "P4_HS_DP_6") (pintype "passive"))
      (node (ref "USB3") (pin "3") (pinfunction "D+_3") (pintype "passive"))
    )
    (net (code "47") (name "/P4_SS_RXA") (class "Default")
      (node (ref "U1") (pin "5") (pinfunction "P4_SS_RXA_5") (pintype "passive"))
      (node (ref "USB3") (pin "5") (pinfunction "STDA_SSRX-_5") (pintype "passive"))
    )
    (net (code "48") (name "/P4_SS_RXB") (class "Default")
      (node (ref "U1") (pin "4") (pinfunction "P4_SS_RXB_4") (pintype "passive"))
      (node (ref "USB3") (pin "6") (pinfunction "STDA_SSRX+_6") (pintype "passive"))
    )
    (net (code "49") (name "/P4_SS_TXA") (class "Default")
      (node (ref "C33") (pin "1") (pinfunction "1_1") (pintype "passive"))
      (node (ref "U1") (pin "2") (pinfunction "P4_SS_TXA_2") (pintype "passive"))
    )
    (net (code "50") (name "/P4_SS_TXB") (class "Default")
      (node (ref "C34") (pin "1") (pinfunction "1_1") (pintype "passive"))
      (node (ref "U1") (pin "1") (pinfunction "P4_SS_TXB_1") (pintype "passive"))
    )
    (net (code "51") (name "/PWREN1") (class "Default")
      (node (ref "R4") (pin "2") (pinfunction "2_2") (pintype "passive"))
      (node (ref "U1") (pin "28") (pinfunction "PWREN1#_28") (pintype "passive"))
    )
    (net (code "52") (name "/PWREN2") (class "Default")
      (node (ref "R16") (pin "2") (pinfunction "2_2") (pintype "passive"))
      (node (ref "U1") (pin "30") (pinfunction "PWREN2#_30") (pintype "passive"))
    )
    (net (code "53") (name "/PWREN3") (class "Default")
      (node (ref "R21") (pin "2") (pinfunction "2_2") (pintype "passive"))
      (node (ref "U1") (pin "32") (pinfunction "PWREN3#_32") (pintype "passive"))
    )
    (net (code "54") (name "/PWREN4") (class "Default")
      (node (ref "R23") (pin "2") (pinfunction "2_2") (pintype "passive"))
      (node (ref "U1") (pin "34") (pinfunction "PWREN4#_34") (pintype "passive"))
    )
    (net (code "55") (name "/SMBDAT") (class "Default")
      (node (ref "R19") (pin "1") (pinfunction "1_1") (pintype "passive"))
      (node (ref "U1") (pin "49") (pinfunction "SMBDAT/SDA_49") (pintype "passive"))
    )
    (net (code "56") (name "/STC_RXD") (class "Default")
      (node (ref "U7") (pin "6") (pinfunction "TXD_6") (pintype "output"))
      (node (ref "U8") (pin "5") (pinfunction "P3.0/RxD_5") (pintype "passive"))
    )
    (net (code "57") (name "/STC_TXD") (class "Default")
      (node (ref "R20") (pin "1") (pinfunction "1_1") (pintype "passive"))
      (node (ref "U7") (pin "7") (pinfunction "RXD_7") (pintype "input"))
      (node (ref "U8") (pin "6") (pinfunction "P3.1/TxD_6") (pintype "passive"))
    )
    (net (code "58") (name "/SUSP{slash}PDHUB") (class "Default")
      (node (ref "LED1") (pin "2") (pinfunction "K_2") (pintype "passive"))
      (node (ref "U1") (pin "44") (pinfunction "SUSP/PDHUB#_44") (pintype "passive"))
    )
    (net (code "59") (name "/UP_HS_DM") (class "Default")
      (node (ref "U1") (pin "63") (pinfunction "UP_HS_DM_63") (pintype "passive"))
      (node (ref "USB4") (pin "2") (pinfunction "D-_2") (pintype "passive"))
    )
    (net (code "60") (name "/UP_HS_DP") (class "Default")
      (node (ref "U1") (pin "62") (pinfunction "UP_HS_DP_62") (pintype "passive"))
      (node (ref "USB4") (pin "3") (pinfunction "D+_3") (pintype "passive"))
    )
    (net (code "61") (name "/UP_SS_RXA") (class "Default")
      (node (ref "U1") (pin "68") (pinfunction "UP_SS_RXA_68") (pintype "passive"))
      (node (ref "USB4") (pin "5") (pinfunction "STDA_SSRX-_5") (pintype "passive"))
    )
    (net (code "62") (name "/UP_SS_RXB") (class "Default")
      (node (ref "U1") (pin "67") (pinfunction "UP_SS_RXB_67") (pintype "passive"))
      (node (ref "USB4") (pin "6") (pinfunction "STDA_SSRX+_6") (pintype "passive"))
    )
    (net (code "63") (name "/UP_SS_TXA") (class "Default")
      (node (ref "C35") (pin "1") (pinfunction "1_1") (pintype "passive"))
      (node (ref "U1") (pin "65") (pinfunction "UP_SS_TXA_65") (pintype "passive"))
    )
    (net (code "64") (name "/UP_SS_TXB") (class "Default")
      (node (ref "C36") (pin "1") (pinfunction "1_1") (pintype "passive"))
      (node (ref "U1") (pin "64") (pinfunction "UP_SS_TXB_64") (pintype "passive"))
    )
    (net (code "65") (name "/X24MI") (class "Default")
      (node (ref "C6") (pin "2") (pinfunction "2_2") (pintype "passive"))
      (node (ref "U1") (pin "48") (pinfunction "XI_48") (pintype "passive"))
      (node (ref "X1") (pin "3") (pinfunction "OUT2_3") (pintype "passive"))
    )
    (net (code "66") (name "/X24MO") (class "Default")
      (node (ref "C7") (pin "2") (pinfunction "2_2") (pintype "passive"))
      (node (ref "U1") (pin "47") (pinfunction "XO_47") (pintype "passive"))
      (node (ref "X1") (pin "1") (pinfunction "OUT1_1") (pintype "passive"))
    )
    (net (code "67") (name "1V2") (class "Default")
      (node (ref "C1") (pin "1") (pinfunction "1_1") (pintype "passive"))
      (node (ref "C2") (pin "1") (pinfunction "1_1") (pintype "passive"))
      (node (ref "C3") (pin "1") (pinfunction "1_1") (pintype "passive"))
      (node (ref "C37") (pin "1") (pinfunction "1_1") (pintype "passive"))
      (node (ref "C38") (pin "1") (pinfunction "1_1") (pintype "passive"))
      (node (ref "C4") (pin "1") (pinfunction "1_1") (pintype "passive"))
      (node (ref "C5") (pin "1") (pinfunction "1_1") (pintype "passive"))
      (node (ref "C8") (pin "1") (pinfunction "1_1") (pintype "passive"))
      (node (ref "C9") (pin "1") (pinfunction "1_1") (pintype "passive"))
      (node (ref "L1") (pin "1") (pinfunction "1_1") (pintype "passive"))
      (node (ref "U1") (pin "12") (pinfunction "P3_VDD12_12") (pintype "passive"))
      (node (ref "U1") (pin "17") (pinfunction "P2_VDD12_17") (pintype "passive"))
      (node (ref "U1") (pin "22") (pinfunction "P2_VDD12_22") (pintype "passive"))
      (node (ref "U1") (pin "3") (pinfunction "P4_VDD12_3") (pintype "passive"))
      (node (ref "U1") (pin "43") (pinfunction "DVDD12_43") (pintype "passive"))
      (node (ref "U1") (pin "52") (pinfunction "P1_VDD12_52") (pintype "passive"))
      (node (ref "U1") (pin "57") (pinfunction "P1_VDD12_57") (pintype "passive"))
      (node (ref "U1") (pin "66") (pinfunction "UP_VDD12_66") (pintype "passive"))
    )
    (net (code "68") (name "3V3") (class "Default")
      (node (ref "C12") (pin "1") (pinfunction "1_1") (pintype "passive"))
      (node (ref "C13") (pin "2") (pinfunction "2_2") (pintype "passive"))
      (node (ref "R11") (pin "1") (pinfunction "1_1") (pintype "passive"))
      (node (ref "R30") (pin "1") (pinfunction "1_1") (pintype "passive"))
      (node (ref "U1") (pin "35") (pinfunction "VDD33_35") (pintype "passive"))
    )
    (net (code "69") (name "GND") (class "Default")
      (node (ref "C1") (pin "2") (pinfunction "2_2") (pintype "passive"))
      (node (ref "C10") (pin "2") (pinfunction "2_2") (pintype "passive"))
      (node (ref "C11") (pin "1") (pinfunction "1_1") (pintype "passive"))
      (node (ref "C12") (pin "2") (pinfunction "2_2") (pintype "passive"))
      (node (ref "C13") (pin "1") (pinfunction "1_1") (pintype "passive"))
      (node (ref "C14") (pin "2") (pinfunction "2_2") (pintype "passive"))
      (node (ref "C15") (pin "2") (pinfunction "2_2") (pintype "passive"))
      (node (ref "C16") (pin "1") (pinfunction "1_1") (pintype "passive"))
      (node (ref "C17") (pin "2") (pinfunction "2_2") (pintype "passive"))
      (node (ref "C18") (pin "2") (pinfunction "2_2") (pintype "passive"))
      (node (ref "C19") (pin "2") (pinfunction "2_2") (pintype "passive"))
      (node (ref "C2") (pin "2") (pinfunction "2_2") (pintype "passive"))
      (node (ref "C20") (pin "1") (pinfunction "1_1") (pintype "passive"))
      (node (ref "C21") (pin "1") (pinfunction "1_1") (pintype "passive"))
      (node (ref "C22") (pin "2") (pinfunction "2_2") (pintype "passive"))
      (node (ref "C27") (pin "2") (pinfunction "2_2") (pintype "passive"))
      (node (ref "C28") (pin "2") (pinfunction "2_2") (pintype "passive"))
      (node (ref "C3") (pin "2") (pinfunction "2_2") (pintype "passive"))
      (node (ref "C31") (pin "2") (pinfunction "2_2") (pintype "passive"))
      (node (ref "C32") (pin "2") (pinfunction "2_2") (pintype "passive"))
      (node (ref "C37") (pin "2") (pinfunction "2_2") (pintype "passive"))
      (node (ref "C38") (pin "2") (pinfunction "2_2") (pintype "passive"))
      (node (ref "C4") (pin "2") (pinfunction "2_2") (pintype "passive"))
      (node (ref "C5") (pin "2") (pinfunction "2_2") (pintype "passive"))
      (node (ref "C6") (pin "1") (pinfunction "1_1") (pintype "passive"))
      (node (ref "C7") (pin "1") (pinfunction "1_1") (pintype "passive"))
      (node (ref "C8") (pin "2") (pinfunction "2_2") (pintype "passive"))
      (node (ref "C9") (pin "2") (pinfunction "2_2") (pintype "passive"))
      (node (ref "D2") (pin "1") (pinfunction "1_1") (pintype "passive"))
      (node (ref "DQ1") (pin "2") (pinfunction "2_2") (pintype "passive"))
      (node (ref "DQ2") (pin "2") (pinfunction "2_2") (pintype "passive"))
      (node (ref "DQ3") (pin "2") (pinfunction "2_2") (pintype "passive"))
      (node (ref "DQ4") (pin "2") (pinfunction "2_2") (pintype "passive"))
      (node (ref "LED3") (pin "2") (pinfunction "K_2") (pintype "passive"))
      (node (ref "LED4") (pin "2") (pinfunction "K_2") (pintype "passive"))
      (node (ref "R14") (pin "2") (pinfunction "2_2") (pintype "passive"))
      (node (ref "R15") (pin "2") (pinfunction "2_2") (pintype "passive"))
      (node (ref "R18") (pin "2") (pinfunction "2_2") (pintype "passive"))
      (node (ref "R19") (pin "2") (pinfunction "2_2") (pintype "passive"))
      (node (ref "R26") (pin "1") (pinfunction "1_1") (pintype "passive"))
      (node (ref "R27") (pin "1") (pinfunction "1_1") (pintype "passive"))
      (node (ref "R3") (pin "1") (pinfunction "1_1") (pintype "passive"))
      (node (ref "R5") (pin "1") (pinfunction "1_1") (pintype "passive"))
      (node (ref "R6") (pin "2") (pinfunction "2_2") (pintype "passive"))
      (node (ref "R7") (pin "1") (pinfunction "1_1") (pintype "passive"))
      (node (ref "R8") (pin "2") (pinfunction "2_2") (pintype "passive"))
      (node (ref "R9") (pin "1") (pinfunction "1_1") (pintype "passive"))
      (node (ref "U1") (pin "69") (pinfunction "GND_69") (pintype "passive"))
      (node (ref "U2") (pin "2") (pinfunction "GND_2") (pintype "passive"))
      (node (ref "U3") (pin "2") (pinfunction "GND_2") (pintype "passive"))
      (node (ref "U4") (pin "1") (pinfunction "A1_1") (pintype "passive"))
      (node (ref "U4") (pin "2") (pinfunction "A0_2") (pintype "passive"))
      (node (ref "U4") (pin "7") (pinfunction "GND_7") (pintype "passive"))
      (node (ref "U5") (pin "2") (pinfunction "GND_2") (pintype "passive"))
      (node (ref "U6") (pin "2") (pinfunction "GND_2") (pintype "passive"))
      (node (ref "U7") (pin "3") (pinfunction "GND_3") (pintype "power_in"))
      (node (ref "U8") (pin "4") (pinfunction "Gnd_4") (pintype "passive"))
      (node (ref "U8") (pin "9") (pinfunction "EP_9") (pintype "passive"))
      (node (ref "USB1") (pin "4") (pinfunction "GND_4") (pintype "passive"))
      (node (ref "USB1") (pin "7") (pinfunction "GND_DRAIN_7") (pintype "passive"))
      (node (ref "USB2") (pin "4") (pinfunction "GND_4") (pintype "passive"))
      (node (ref "USB2") (pin "7") (pinfunction "GND_DRAIN_7") (pintype "passive"))
      (node (ref "USB3") (pin "4") (pinfunction "GND_4") (pintype "passive"))
      (node (ref "USB3") (pin "7") (pinfunction "GND_DRAIN_7") (pintype "passive"))
      (node (ref "USB4") (pin "4") (pinfunction "GND_4") (pintype "passive"))
      (node (ref "USB4") (pin "7") (pinfunction "GND_DRAIN_7") (pintype "passive"))
      (node (ref "USB6") (pin "A1") (pinfunction "GND_A1") (pintype "passive"))
      (node (ref "USB6") (pin "A12") (pinfunction "GND_A12") (pintype "passive"))
      (node (ref "USB6") (pin "B1") (pinfunction "GND_B1") (pintype "passive"))
      (node (ref "USB6") (pin "B12") (pinfunction "GND_B12") (pintype "passive"))
      (node (ref "USB7") (pin "A1") (pinfunction "GND_A1") (pintype "passive"))
      (node (ref "USB7") (pin "A12") (pinfunction "GND_A12") (pintype "passive"))
      (node (ref "USB7") (pin "B1") (pinfunction "GND_B1") (pintype "passive"))
      (node (ref "USB7") (pin "B12") (pinfunction "GND_B12") (pintype "passive"))
      (node (ref "X1") (pin "2") (pinfunction "GND1_2") (pintype "passive"))
      (node (ref "X1") (pin "4") (pinfunction "GND2_4") (pintype "passive"))
    )
    (net (code "70") (name "Net-(DQ1-Pad1)") (class "Default")
      (node (ref "DQ1") (pin "1") (pinfunction "1_1") (pintype "passive"))
      (node (ref "R4") (pin "1") (pinfunction "1_1") (pintype "passive"))
    )
    (net (code "71") (name "Net-(DQ2-Pad1)") (class "Default")
      (node (ref "DQ2") (pin "1") (pinfunction "1_1") (pintype "passive"))
      (node (ref "R16") (pin "1") (pinfunction "1_1") (pintype "passive"))
    )
    (net (code "72") (name "Net-(DQ3-Pad1)") (class "Default")
      (node (ref "DQ3") (pin "1") (pinfunction "1_1") (pintype "passive"))
      (node (ref "R21") (pin "1") (pinfunction "1_1") (pintype "passive"))
    )
    (net (code "73") (name "Net-(DQ4-Pad1)") (class "Default")
      (node (ref "DQ4") (pin "1") (pinfunction "1_1") (pintype "passive"))
      (node (ref "R23") (pin "1") (pinfunction "1_1") (pintype "passive"))
    )
    (net (code "74") (name "Net-(JP1-Pad1)") (class "Default")
      (node (ref "JP1") (pin "1") (pinfunction "1_1") (pintype "passive"))
      (node (ref "USB6") (pin "A4") (pinfunction "VBUS_A4") (pintype "passive"))
      (node (ref "USB6") (pin "A9") (pinfunction "VBUS_A9") (pintype "passive"))
      (node (ref "USB6") (pin "B4") (pinfunction "VBUS_B4") (pintype "passive"))
      (node (ref "USB6") (pin "B9") (pinfunction "VBUS_B9") (pintype "passive"))
    )
    (net (code "75") (name "Net-(LED1-A)") (class "Default")
      (node (ref "LED1") (pin "1") (pinfunction "A_1") (pintype "passive"))
      (node (ref "R11") (pin "2") (pinfunction "2_2") (pintype "passive"))
    )
    (net (code "76") (name "Net-(LED2-A)") (class "Default")
      (node (ref "LED2") (pin "1") (pinfunction "A_1") (pintype "passive"))
      (node (ref "R30") (pin "2") (pinfunction "2_2") (pintype "passive"))
    )
    (net (code "77") (name "Net-(LED3-A)") (class "Default")
      (node (ref "LED3") (pin "1") (pinfunction "A_1") (pintype "passive"))
      (node (ref "R31") (pin "2") (pinfunction "2_2") (pintype "passive"))
    )
    (net (code "78") (name "Net-(LED4-A)") (class "Default")
      (node (ref "LED4") (pin "1") (pinfunction "A_1") (pintype "passive"))
      (node (ref "R20") (pin "2") (pinfunction "2_2") (pintype "passive"))
    )
    (net (code "79") (name "Net-(U1-VSW)") (class "Default")
      (node (ref "L1") (pin "2") (pinfunction "2_2") (pintype "passive"))
      (node (ref "U1") (pin "37") (pinfunction "VSW_37") (pintype "passive"))
    )
    (net (code "80") (name "Net-(U2-EN)") (class "Default")
      (node (ref "DQ1") (pin "3") (pinfunction "3_3") (pintype "passive"))
      (node (ref "R2") (pin "1") (pinfunction "1_1") (pintype "passive"))
      (node (ref "U2") (pin "4") (pinfunction "EN_4") (pintype "passive"))
    )
    (net (code "81") (name "Net-(U2-SET)") (class "Default")
      (node (ref "R3") (pin "2") (pinfunction "2_2") (pintype "passive"))
      (node (ref "U2") (pin "3") (pinfunction "SET_3") (pintype "passive"))
    )
    (net (code "82") (name "Net-(U3-EN)") (class "Default")
      (node (ref "DQ2") (pin "3") (pinfunction "3_3") (pintype "passive"))
      (node (ref "R10") (pin "1") (pinfunction "1_1") (pintype "passive"))
      (node (ref "U3") (pin "4") (pinfunction "EN_4") (pintype "passive"))
    )
    (net (code "83") (name "Net-(U3-SET)") (class "Default")
      (node (ref "R5") (pin "2") (pinfunction "2_2") (pintype "passive"))
      (node (ref "U3") (pin "3") (pinfunction "SET_3") (pintype "passive"))
    )
    (net (code "84") (name "Net-(U4-VIN+)") (class "Default")
      (node (ref "R1") (pin "2") (pinfunction "2_2") (pintype "passive"))
      (node (ref "U4") (pin "10") (pinfunction "VIN+_10") (pintype "passive"))
      (node (ref "USB7") (pin "A4") (pinfunction "VBUS_A4") (pintype "passive"))
      (node (ref "USB7") (pin "A9") (pinfunction "VBUS_A9") (pintype "passive"))
      (node (ref "USB7") (pin "B4") (pinfunction "VBUS_B4") (pintype "passive"))
      (node (ref "USB7") (pin "B9") (pinfunction "VBUS_B9") (pintype "passive"))
    )
    (net (code "85") (name "Net-(U5-EN)") (class "Default")
      (node (ref "DQ3") (pin "3") (pinfunction "3_3") (pintype "passive"))
      (node (ref "R17") (pin "1") (pinfunction "1_1") (pintype "passive"))
      (node (ref "U5") (pin "4") (pinfunction "EN_4") (pintype "passive"))
    )
    (net (code "86") (name "Net-(U5-SET)") (class "Default")
      (node (ref "R7") (pin "2") (pinfunction "2_2") (pintype "passive"))
      (node (ref "U5") (pin "3") (pinfunction "SET_3") (pintype "passive"))
    )
    (net (code "87") (name "Net-(U6-EN)") (class "Default")
      (node (ref "DQ4") (pin "3") (pinfunction "3_3") (pintype "passive"))
      (node (ref "R22") (pin "1") (pinfunction "1_1") (pintype "passive"))
      (node (ref "U6") (pin "4") (pinfunction "EN_4") (pintype "passive"))
    )
    (net (code "88") (name "Net-(U6-SET)") (class "Default")
      (node (ref "R9") (pin "2") (pinfunction "2_2") (pintype "passive"))
      (node (ref "U6") (pin "3") (pinfunction "SET_3") (pintype "passive"))
    )
    (net (code "89") (name "Net-(U7-V3)") (class "Default")
      (node (ref "C19") (pin "1") (pinfunction "1_1") (pintype "passive"))
      (node (ref "U7") (pin "8") (pinfunction "V3_8") (pintype "power_in"))
    )
    (net (code "90") (name "Net-(USB1-D+)") (class "Default")
      (node (ref "R29") (pin "2") (pinfunction "2_2") (pintype "passive"))
      (node (ref "USB1") (pin "3") (pinfunction "D+_3") (pintype "passive"))
    )
    (net (code "91") (name "Net-(USB1-D-)") (class "Default")
      (node (ref "R28") (pin "2") (pinfunction "2_2") (pintype "passive"))
      (node (ref "USB1") (pin "2") (pinfunction "D-_2") (pintype "passive"))
    )
    (net (code "92") (name "Net-(USB1-STDA_SSTX+)") (class "Default")
      (node (ref "C26") (pin "2") (pinfunction "2_2") (pintype "passive"))
      (node (ref "USB1") (pin "9") (pinfunction "STDA_SSTX+_9") (pintype "passive"))
    )
    (net (code "93") (name "Net-(USB1-STDA_SSTX-)") (class "Default")
      (node (ref "C25") (pin "2") (pinfunction "2_2") (pintype "passive"))
      (node (ref "USB1") (pin "8") (pinfunction "STDA_SSTX-_8") (pintype "passive"))
    )
    (net (code "94") (name "Net-(USB3-STDA_SSTX+)") (class "Default")
      (node (ref "C34") (pin "2") (pinfunction "2_2") (pintype "passive"))
      (node (ref "USB3") (pin "9") (pinfunction "STDA_SSTX+_9") (pintype "passive"))
    )
    (net (code "95") (name "Net-(USB3-STDA_SSTX-)") (class "Default")
      (node (ref "C33") (pin "2") (pinfunction "2_2") (pintype "passive"))
      (node (ref "USB3") (pin "8") (pinfunction "STDA_SSTX-_8") (pintype "passive"))
    )
    (net (code "96") (name "Net-(USB4-STDA_SSTX+)") (class "Default")
      (node (ref "C36") (pin "2") (pinfunction "2_2") (pintype "passive"))
      (node (ref "USB4") (pin "9") (pinfunction "STDA_SSTX+_9") (pintype "passive"))
    )
    (net (code "97") (name "Net-(USB4-STDA_SSTX-)") (class "Default")
      (node (ref "C35") (pin "2") (pinfunction "2_2") (pintype "passive"))
      (node (ref "USB4") (pin "8") (pinfunction "STDA_SSTX-_8") (pintype "passive"))
    )
    (net (code "98") (name "Net-(USB6-CC1)") (class "Default")
      (node (ref "R26") (pin "2") (pinfunction "2_2") (pintype "passive"))
      (node (ref "USB6") (pin "A5") (pinfunction "CC1_A5") (pintype "passive"))
    )
    (net (code "99") (name "Net-(USB6-CC2)") (class "Default")
      (node (ref "R27") (pin "2") (pinfunction "2_2") (pintype "passive"))
      (node (ref "USB6") (pin "B5") (pinfunction "CC2_B5") (pintype "passive"))
    )
    (net (code "100") (name "Vusb") (class "Default")
      (node (ref "C10") (pin "1") (pinfunction "1_1") (pintype "passive"))
      (node (ref "C11") (pin "2") (pinfunction "2_2") (pintype "passive"))
      (node (ref "C16") (pin "2") (pinfunction "2_2") (pintype "passive"))
      (node (ref "C20") (pin "2") (pinfunction "2_2") (pintype "passive"))
      (node (ref "C21") (pin "2") (pinfunction "2_2") (pintype "passive"))
      (node (ref "C22") (pin "1") (pinfunction "1_1") (pintype "passive"))
      (node (ref "C27") (pin "1") (pinfunction "1_1") (pintype "passive"))
      (node (ref "C28") (pin "1") (pinfunction "1_1") (pintype "passive"))
      (node (ref "C31") (pin "1") (pinfunction "1_1") (pintype "passive"))
      (node (ref "C32") (pin "1") (pinfunction "1_1") (pintype "passive"))
      (node (ref "D2") (pin "2") (pinfunction "2_2") (pintype "passive"))
      (node (ref "JP1") (pin "2") (pinfunction "2_2") (pintype "passive"))
      (node (ref "R1") (pin "1") (pinfunction "1_1") (pintype "passive"))
      (node (ref "R10") (pin "2") (pinfunction "2_2") (pintype "passive"))
      (node (ref "R12") (pin "1") (pinfunction "1_1") (pintype "passive"))
      (node (ref "R13") (pin "1") (pinfunction "1_1") (pintype "passive"))
      (node (ref "R17") (pin "2") (pinfunction "2_2") (pintype "passive"))
      (node (ref "R2") (pin "2") (pinfunction "2_2") (pintype "passive"))
      (node (ref "R22") (pin "2") (pinfunction "2_2") (pintype "passive"))
      (node (ref "U1") (pin "36") (pinfunction "VDD5_36") (pintype "passive"))
      (node (ref "U2") (pin "5") (pinfunction "VIN_5") (pintype "passive"))
      (node (ref "U3") (pin "5") (pinfunction "VIN_5") (pintype "passive"))
      (node (ref "U4") (pin "6") (pinfunction "VS+_6") (pintype "passive"))
      (node (ref "U4") (pin "8") (pinfunction "VBUS_8") (pintype "passive"))
      (node (ref "U4") (pin "9") (pinfunction "VIN-_9") (pintype "passive"))
      (node (ref "U5") (pin "5") (pinfunction "VIN_5") (pintype "passive"))
      (node (ref "U6") (pin "5") (pinfunction "VIN_5") (pintype "passive"))
      (node (ref "U7") (pin "5") (pinfunction "VCC_5") (pintype "power_in"))
      (node (ref "U8") (pin "2") (pinfunction "Vcc_2") (pintype "passive"))
    )
    (net (code "101") (name "Vusb1") (class "Default")
      (node (ref "C14") (pin "1") (pinfunction "1_1") (pintype "passive"))
      (node (ref "U2") (pin "1") (pinfunction "VOUT_1") (pintype "passive"))
      (node (ref "USB4") (pin "1") (pinfunction "VBUS_1") (pintype "passive"))
    )
    (net (code "102") (name "Vusb2") (class "Default")
      (node (ref "C15") (pin "1") (pinfunction "1_1") (pintype "passive"))
      (node (ref "U3") (pin "1") (pinfunction "VOUT_1") (pintype "passive"))
      (node (ref "USB1") (pin "1") (pinfunction "VBUS_1") (pintype "passive"))
    )
    (net (code "103") (name "Vusb3") (class "Default")
      (node (ref "C17") (pin "1") (pinfunction "1_1") (pintype "passive"))
      (node (ref "U5") (pin "1") (pinfunction "VOUT_1") (pintype "passive"))
      (node (ref "USB2") (pin "1") (pinfunction "VBUS_1") (pintype "passive"))
    )
    (net (code "104") (name "Vusb4") (class "Default")
      (node (ref "C18") (pin "1") (pinfunction "1_1") (pintype "passive"))
      (node (ref "U6") (pin "1") (pinfunction "VOUT_1") (pintype "passive"))
      (node (ref "USB3") (pin "1") (pinfunction "VBUS_1") (pintype "passive"))
    )
    (net (code "105") (name "unconnected-(U1-NC-Pad38)") (class "Default")
      (node (ref "U1") (pin "38") (pinfunction "NC_38") (pintype "passive"))
    )
    (net (code "106") (name "unconnected-(U7-RTS#-Pad4)") (class "Default")
      (node (ref "U7") (pin "4") (pinfunction "RTS#_4") (pintype "output"))
    )
    (net (code "107") (name "unconnected-(USB1-Pad10)") (class "Default")
      (node (ref "USB1") (pin "10") (pinfunction "10_10") (pintype "passive"))
    )
    (net (code "108") (name "unconnected-(USB1-Pad11)") (class "Default")
      (node (ref "USB1") (pin "11") (pinfunction "11_11") (pintype "passive"))
    )
    (net (code "109") (name "unconnected-(USB1-Pad12)") (class "Default")
      (node (ref "USB1") (pin "12") (pinfunction "12_12") (pintype "passive"))
    )
    (net (code "110") (name "unconnected-(USB1-Pad13)") (class "Default")
      (node (ref "USB1") (pin "13") (pinfunction "13_13") (pintype "passive"))
    )
    (net (code "111") (name "unconnected-(USB2-Pad10)") (class "Default")
      (node (ref "USB2") (pin "10") (pinfunction "10_10") (pintype "passive"))
    )
    (net (code "112") (name "unconnected-(USB2-Pad11)") (class "Default")
      (node (ref "USB2") (pin "11") (pinfunction "11_11") (pintype "passive"))
    )
    (net (code "113") (name "unconnected-(USB2-Pad12)") (class "Default")
      (node (ref "USB2") (pin "12") (pinfunction "12_12") (pintype "passive"))
    )
    (net (code "114") (name "unconnected-(USB2-Pad13)") (class "Default")
      (node (ref "USB2") (pin "13") (pinfunction "13_13") (pintype "passive"))
    )
    (net (code "115") (name "unconnected-(USB3-Pad10)") (class "Default")
      (node (ref "USB3") (pin "10") (pinfunction "10_10") (pintype "passive"))
    )
    (net (code "116") (name "unconnected-(USB3-Pad11)") (class "Default")
      (node (ref "USB3") (pin "11") (pinfunction "11_11") (pintype "passive"))
    )
    (net (code "117") (name "unconnected-(USB3-Pad12)") (class "Default")
      (node (ref "USB3") (pin "12") (pinfunction "12_12") (pintype "passive"))
    )
    (net (code "118") (name "unconnected-(USB3-Pad13)") (class "Default")
      (node (ref "USB3") (pin "13") (pinfunction "13_13") (pintype "passive"))
    )
    (net (code "119") (name "unconnected-(USB4-Pad10)") (class "Default")
      (node (ref "USB4") (pin "10") (pinfunction "10_10") (pintype "passive"))
    )
    (net (code "120") (name "unconnected-(USB4-Pad11)") (class "Default")
      (node (ref "USB4") (pin "11") (pinfunction "11_11") (pintype "passive"))
    )
    (net (code "121") (name "unconnected-(USB4-Pad12)") (class "Default")
      (node (ref "USB4") (pin "12") (pinfunction "12_12") (pintype "passive"))
    )
    (net (code "122") (name "unconnected-(USB4-Pad13)") (class "Default")
      (node (ref "USB4") (pin "13") (pinfunction "13_13") (pintype "passive"))
    )
    (net (code "123") (name "unconnected-(USB6-EP-Pad1)") (class "Default")
      (node (ref "USB6") (pin "1") (pinfunction "EP_1") (pintype "passive"))
    )
    (net (code "124") (name "unconnected-(USB6-EP-Pad2)") (class "Default")
      (node (ref "USB6") (pin "2") (pinfunction "EP_2") (pintype "passive"))
    )
    (net (code "125") (name "unconnected-(USB6-EP-Pad3)") (class "Default")
      (node (ref "USB6") (pin "3") (pinfunction "EP_3") (pintype "passive"))
    )
    (net (code "126") (name "unconnected-(USB6-EP-Pad4)") (class "Default")
      (node (ref "USB6") (pin "4") (pinfunction "EP_4") (pintype "passive"))
    )
    (net (code "127") (name "unconnected-(USB6-SUB1-PadA8)") (class "Default")
      (node (ref "USB6") (pin "A8") (pinfunction "SUB1_A8") (pintype "passive"))
    )
    (net (code "128") (name "unconnected-(USB6-SUB2-PadB8)") (class "Default")
      (node (ref "USB6") (pin "B8") (pinfunction "SUB2_B8") (pintype "passive"))
    )
    (net (code "129") (name "unconnected-(USB7-GND-Pad25)") (class "Default")
      (node (ref "USB7") (pin "25") (pinfunction "GND_25") (pintype "passive"))
    )
    (net (code "130") (name "unconnected-(USB7-GND-Pad26)") (class "Default")
      (node (ref "USB7") (pin "26") (pinfunction "GND_26") (pintype "passive"))
    )
    (net (code "131") (name "unconnected-(USB7-GND-Pad27)") (class "Default")
      (node (ref "USB7") (pin "27") (pinfunction "GND_27") (pintype "passive"))
    )
    (net (code "132") (name "unconnected-(USB7-GND-Pad28)") (class "Default")
      (node (ref "USB7") (pin "28") (pinfunction "GND_28") (pintype "passive"))
    )
    (net (code "133") (name "unconnected-(USB7-SBU1-PadA8)") (class "Default")
      (node (ref "USB7") (pin "A8") (pinfunction "SBU1_A8") (pintype "passive"))
    )
    (net (code "134") (name "unconnected-(USB7-SBU2-PadB8)") (class "Default")
      (node (ref "USB7") (pin "B8") (pinfunction "SBU2_B8") (pintype "passive"))
    )
  )
)
